# ACRoBaT_-_led_board.net
KiCad netlist of a schematic drawn in EAGLE
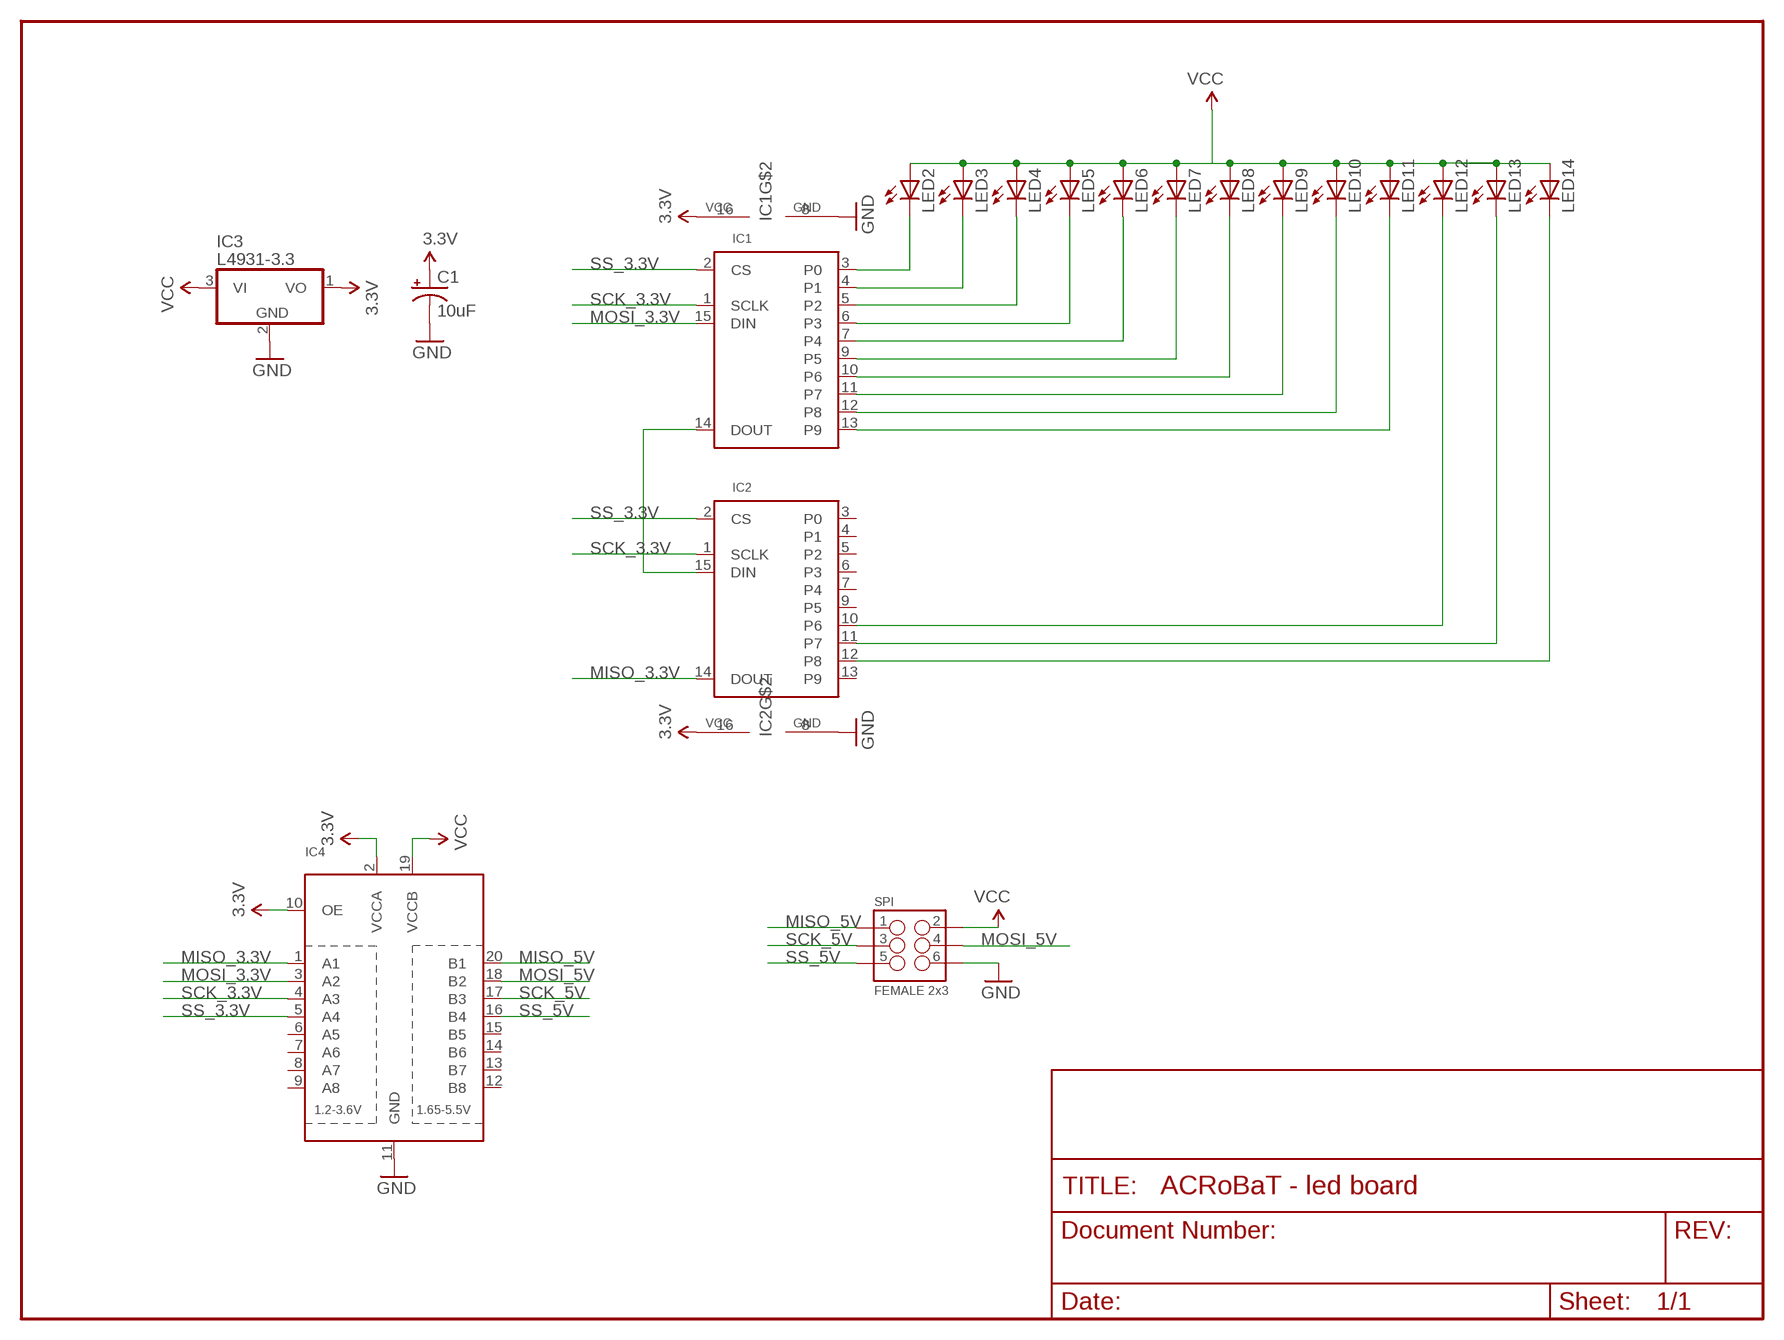
[diagram p0: schematic, sheet 1]

(export (version "E")
  (design (tool "Eeschema 10.0.6"))
  (components
    (comp (ref "C1")
      (value "10uF")
      (footprint "eagle-import:CPOL-RADIAL-10UF-25V")
      (libsource (lib "eagle-import") (part "CAP_POLPTH2"))
    )
    (comp (ref "IC1")
      (value "MAX6966AEE")
      (footprint "eagle-import:QSOP16")
      (libsource (lib "eagle-import") (part "MAX6966AEE"))
    )
    (comp (ref "IC2")
      (value "MAX6966AEE")
      (footprint "eagle-import:QSOP16")
      (libsource (lib "eagle-import") (part "MAX6966AEE"))
    )
    (comp (ref "IC3")
      (value "L4931-3.3")
      (footprint "eagle-import:TO92")
      (libsource (lib "eagle-import") (part "78ZL05"))
    )
    (comp (ref "IC4")
      (value "TXB0108PWR")
      (footprint "eagle-import:TSSOP20")
      (libsource (lib "eagle-import") (part "TXB0108PWR"))
    )
    (comp (ref "LED2")
      (value "LED5MM")
      (footprint "eagle-import:LED5MM")
      (libsource (lib "eagle-import") (part "LED5MM"))
    )
    (comp (ref "LED3")
      (value "LED5MM")
      (footprint "eagle-import:LED5MM")
      (libsource (lib "eagle-import") (part "LED5MM"))
    )
    (comp (ref "LED4")
      (value "LED5MM")
      (footprint "eagle-import:LED5MM")
      (libsource (lib "eagle-import") (part "LED5MM"))
    )
    (comp (ref "LED5")
      (value "LED5MM")
      (footprint "eagle-import:LED5MM")
      (libsource (lib "eagle-import") (part "LED5MM"))
    )
    (comp (ref "LED6")
      (value "LED5MM")
      (footprint "eagle-import:LED5MM")
      (libsource (lib "eagle-import") (part "LED5MM"))
    )
    (comp (ref "LED7")
      (value "LED5MM")
      (footprint "eagle-import:LED5MM")
      (libsource (lib "eagle-import") (part "LED5MM"))
    )
    (comp (ref "LED8")
      (value "LED5MM")
      (footprint "eagle-import:LED5MM")
      (libsource (lib "eagle-import") (part "LED5MM"))
    )
    (comp (ref "LED9")
      (value "LED5MM")
      (footprint "eagle-import:LED5MM")
      (libsource (lib "eagle-import") (part "LED5MM"))
    )
    (comp (ref "LED10")
      (value "LED5MM")
      (footprint "eagle-import:LED5MM")
      (libsource (lib "eagle-import") (part "LED5MM"))
    )
    (comp (ref "LED11")
      (value "LED5MM")
      (footprint "eagle-import:LED5MM")
      (libsource (lib "eagle-import") (part "LED5MM"))
    )
    (comp (ref "LED12")
      (value "LED5MM")
      (footprint "eagle-import:LED5MM")
      (libsource (lib "eagle-import") (part "LED5MM"))
    )
    (comp (ref "LED13")
      (value "LED5MM")
      (footprint "eagle-import:LED5MM")
      (libsource (lib "eagle-import") (part "LED5MM"))
    )
    (comp (ref "LED14")
      (value "LED5MM")
      (footprint "eagle-import:LED5MM")
      (libsource (lib "eagle-import") (part "LED5MM"))
    )
    (comp (ref "SPI")
      (value "FEMALE 2x3")
      (footprint "eagle-import:2X3")
      (libsource (lib "eagle-import") (part "M03X2FEMALE"))
    )
  )
  (nets
    (net (code "1") (name "/MISO_3.3V") (class "Default")
      (node (ref "IC2") (pin "14") (pinfunction "DOUT_14") (pintype "output"))
      (node (ref "IC4") (pin "1") (pinfunction "A1_1") (pintype "bidirectional"))
    )
    (net (code "2") (name "/MISO_5V") (class "Default")
      (node (ref "IC4") (pin "20") (pinfunction "B1_20") (pintype "bidirectional"))
      (node (ref "SPI") (pin "1") (pinfunction "1_1") (pintype "bidirectional"))
    )
    (net (code "3") (name "/MOSI_3.3V") (class "Default")
      (node (ref "IC1") (pin "15") (pinfunction "DIN_15") (pintype "input"))
      (node (ref "IC4") (pin "3") (pinfunction "A2_3") (pintype "bidirectional"))
    )
    (net (code "4") (name "/MOSI_5V") (class "Default")
      (node (ref "IC4") (pin "18") (pinfunction "B2_18") (pintype "bidirectional"))
      (node (ref "SPI") (pin "4") (pinfunction "4_4") (pintype "bidirectional"))
    )
    (net (code "5") (name "/SCK_3.3V") (class "Default")
      (node (ref "IC1") (pin "1") (pinfunction "SCLK_1") (pintype "input"))
      (node (ref "IC2") (pin "1") (pinfunction "SCLK_1") (pintype "input"))
      (node (ref "IC4") (pin "4") (pinfunction "A3_4") (pintype "bidirectional"))
    )
    (net (code "6") (name "/SCK_5V") (class "Default")
      (node (ref "IC4") (pin "17") (pinfunction "B3_17") (pintype "bidirectional"))
      (node (ref "SPI") (pin "3") (pinfunction "3_3") (pintype "bidirectional"))
    )
    (net (code "7") (name "/SS_3.3V") (class "Default")
      (node (ref "IC1") (pin "2") (pinfunction "CS_2") (pintype "input"))
      (node (ref "IC2") (pin "2") (pinfunction "CS_2") (pintype "input"))
      (node (ref "IC4") (pin "5") (pinfunction "A4_5") (pintype "bidirectional"))
    )
    (net (code "8") (name "/SS_5V") (class "Default")
      (node (ref "IC4") (pin "16") (pinfunction "B4_16") (pintype "bidirectional"))
      (node (ref "SPI") (pin "5") (pinfunction "5_5") (pintype "bidirectional"))
    )
    (net (code "9") (name "3.3V") (class "Default")
      (node (ref "C1") (pin "1") (pinfunction "+_1") (pintype "passive"))
      (node (ref "IC1") (pin "16") (pinfunction "VCC_16") (pintype "power_in"))
      (node (ref "IC2") (pin "16") (pinfunction "VCC_16") (pintype "power_in"))
      (node (ref "IC3") (pin "1") (pinfunction "VO_1") (pintype "passive"))
      (node (ref "IC4") (pin "10") (pinfunction "OE_10") (pintype "bidirectional"))
      (node (ref "IC4") (pin "2") (pinfunction "VCCA_2") (pintype "bidirectional"))
    )
    (net (code "10") (name "GND") (class "Default")
      (node (ref "C1") (pin "2") (pinfunction "-_2") (pintype "passive"))
      (node (ref "IC1") (pin "8") (pinfunction "GND_8") (pintype "power_in"))
      (node (ref "IC2") (pin "8") (pinfunction "GND_8") (pintype "power_in"))
      (node (ref "IC3") (pin "2") (pinfunction "GND_2") (pintype "passive"))
      (node (ref "IC4") (pin "11") (pinfunction "GND_11") (pintype "bidirectional"))
      (node (ref "SPI") (pin "6") (pinfunction "6_6") (pintype "bidirectional"))
    )
    (net (code "11") (name "Net-(IC1A-DOUT)") (class "Default")
      (node (ref "IC1") (pin "14") (pinfunction "DOUT_14") (pintype "output"))
      (node (ref "IC2") (pin "15") (pinfunction "DIN_15") (pintype "input"))
    )
    (net (code "12") (name "Net-(IC1A-P0)") (class "Default")
      (node (ref "IC1") (pin "3") (pinfunction "P0_3") (pintype "output"))
      (node (ref "LED2") (pin "K") (pinfunction "C_K") (pintype "passive"))
    )
    (net (code "13") (name "Net-(IC1A-P1)") (class "Default")
      (node (ref "IC1") (pin "4") (pinfunction "P1_4") (pintype "output"))
      (node (ref "LED3") (pin "K") (pinfunction "C_K") (pintype "passive"))
    )
    (net (code "14") (name "Net-(IC1A-P2)") (class "Default")
      (node (ref "IC1") (pin "5") (pinfunction "P2_5") (pintype "output"))
      (node (ref "LED4") (pin "K") (pinfunction "C_K") (pintype "passive"))
    )
    (net (code "15") (name "Net-(IC1A-P3)") (class "Default")
      (node (ref "IC1") (pin "6") (pinfunction "P3_6") (pintype "output"))
      (node (ref "LED5") (pin "K") (pinfunction "C_K") (pintype "passive"))
    )
    (net (code "16") (name "Net-(IC1A-P4)") (class "Default")
      (node (ref "IC1") (pin "7") (pinfunction "P4_7") (pintype "output"))
      (node (ref "LED6") (pin "K") (pinfunction "C_K") (pintype "passive"))
    )
    (net (code "17") (name "Net-(IC1A-P5)") (class "Default")
      (node (ref "IC1") (pin "9") (pinfunction "P5_9") (pintype "output"))
      (node (ref "LED7") (pin "K") (pinfunction "C_K") (pintype "passive"))
    )
    (net (code "18") (name "Net-(IC1A-P6)") (class "Default")
      (node (ref "IC1") (pin "10") (pinfunction "P6_10") (pintype "output"))
      (node (ref "LED8") (pin "K") (pinfunction "C_K") (pintype "passive"))
    )
    (net (code "19") (name "Net-(IC1A-P7)") (class "Default")
      (node (ref "IC1") (pin "11") (pinfunction "P7_11") (pintype "output"))
      (node (ref "LED9") (pin "K") (pinfunction "C_K") (pintype "passive"))
    )
    (net (code "20") (name "Net-(IC1A-P8)") (class "Default")
      (node (ref "IC1") (pin "12") (pinfunction "P8_12") (pintype "output"))
      (node (ref "LED10") (pin "K") (pinfunction "C_K") (pintype "passive"))
    )
    (net (code "21") (name "Net-(IC1A-P9)") (class "Default")
      (node (ref "IC1") (pin "13") (pinfunction "P9_13") (pintype "output"))
      (node (ref "LED11") (pin "K") (pinfunction "C_K") (pintype "passive"))
    )
    (net (code "22") (name "Net-(IC2A-P6)") (class "Default")
      (node (ref "IC2") (pin "10") (pinfunction "P6_10") (pintype "output"))
      (node (ref "LED12") (pin "K") (pinfunction "C_K") (pintype "passive"))
    )
    (net (code "23") (name "Net-(IC2A-P7)") (class "Default")
      (node (ref "IC2") (pin "11") (pinfunction "P7_11") (pintype "output"))
      (node (ref "LED13") (pin "K") (pinfunction "C_K") (pintype "passive"))
    )
    (net (code "24") (name "Net-(IC2A-P8)") (class "Default")
      (node (ref "IC2") (pin "12") (pinfunction "P8_12") (pintype "output"))
      (node (ref "LED14") (pin "K") (pinfunction "C_K") (pintype "passive"))
    )
    (net (code "25") (name "VCC") (class "Default")
      (node (ref "IC3") (pin "3") (pinfunction "VI_3") (pintype "input"))
      (node (ref "IC4") (pin "19") (pinfunction "VCCB_19") (pintype "bidirectional"))
      (node (ref "LED10") (pin "A") (pinfunction "A_A") (pintype "passive"))
      (node (ref "LED11") (pin "A") (pinfunction "A_A") (pintype "passive"))
      (node (ref "LED12") (pin "A") (pinfunction "A_A") (pintype "passive"))
      (node (ref "LED13") (pin "A") (pinfunction "A_A") (pintype "passive"))
      (node (ref "LED14") (pin "A") (pinfunction "A_A") (pintype "passive"))
      (node (ref "LED2") (pin "A") (pinfunction "A_A") (pintype "passive"))
      (node (ref "LED3") (pin "A") (pinfunction "A_A") (pintype "passive"))
      (node (ref "LED4") (pin "A") (pinfunction "A_A") (pintype "passive"))
      (node (ref "LED5") (pin "A") (pinfunction "A_A") (pintype "passive"))
      (node (ref "LED6") (pin "A") (pinfunction "A_A") (pintype "passive"))
      (node (ref "LED7") (pin "A") (pinfunction "A_A") (pintype "passive"))
      (node (ref "LED8") (pin "A") (pinfunction "A_A") (pintype "passive"))
      (node (ref "LED9") (pin "A") (pinfunction "A_A") (pintype "passive"))
      (node (ref "SPI") (pin "2") (pinfunction "2_2") (pintype "bidirectional"))
    )
    (net (code "26") (name "unconnected-(IC2A-P0-Pad3)") (class "Default")
      (node (ref "IC2") (pin "3") (pinfunction "P0_3") (pintype "output"))
    )
    (net (code "27") (name "unconnected-(IC2A-P1-Pad4)") (class "Default")
      (node (ref "IC2") (pin "4") (pinfunction "P1_4") (pintype "output"))
    )
    (net (code "28") (name "unconnected-(IC2A-P2-Pad5)") (class "Default")
      (node (ref "IC2") (pin "5") (pinfunction "P2_5") (pintype "output"))
    )
    (net (code "29") (name "unconnected-(IC2A-P3-Pad6)") (class "Default")
      (node (ref "IC2") (pin "6") (pinfunction "P3_6") (pintype "output"))
    )
    (net (code "30") (name "unconnected-(IC2A-P4-Pad7)") (class "Default")
      (node (ref "IC2") (pin "7") (pinfunction "P4_7") (pintype "output"))
    )
    (net (code "31") (name "unconnected-(IC2A-P5-Pad9)") (class "Default")
      (node (ref "IC2") (pin "9") (pinfunction "P5_9") (pintype "output"))
    )
    (net (code "32") (name "unconnected-(IC2A-P9-Pad13)") (class "Default")
      (node (ref "IC2") (pin "13") (pinfunction "P9_13") (pintype "output"))
    )
    (net (code "33") (name "unconnected-(IC4-A5-Pad6)") (class "Default")
      (node (ref "IC4") (pin "6") (pinfunction "A5_6") (pintype "bidirectional"))
    )
    (net (code "34") (name "unconnected-(IC4-A6-Pad7)") (class "Default")
      (node (ref "IC4") (pin "7") (pinfunction "A6_7") (pintype "bidirectional"))
    )
    (net (code "35") (name "unconnected-(IC4-A7-Pad8)") (class "Default")
      (node (ref "IC4") (pin "8") (pinfunction "A7_8") (pintype "bidirectional"))
    )
    (net (code "36") (name "unconnected-(IC4-A8-Pad9)") (class "Default")
      (node (ref "IC4") (pin "9") (pinfunction "A8_9") (pintype "bidirectional"))
    )
    (net (code "37") (name "unconnected-(IC4-B5-Pad15)") (class "Default")
      (node (ref "IC4") (pin "15") (pinfunction "B5_15") (pintype "bidirectional"))
    )
    (net (code "38") (name "unconnected-(IC4-B6-Pad14)") (class "Default")
      (node (ref "IC4") (pin "14") (pinfunction "B6_14") (pintype "bidirectional"))
    )
    (net (code "39") (name "unconnected-(IC4-B7-Pad13)") (class "Default")
      (node (ref "IC4") (pin "13") (pinfunction "B7_13") (pintype "bidirectional"))
    )
    (net (code "40") (name "unconnected-(IC4-B8-Pad12)") (class "Default")
      (node (ref "IC4") (pin "12") (pinfunction "B8_12") (pintype "bidirectional"))
    )
  )
)
